# Esquema.net
KiCad netlist of a schematic drawn in EAGLE
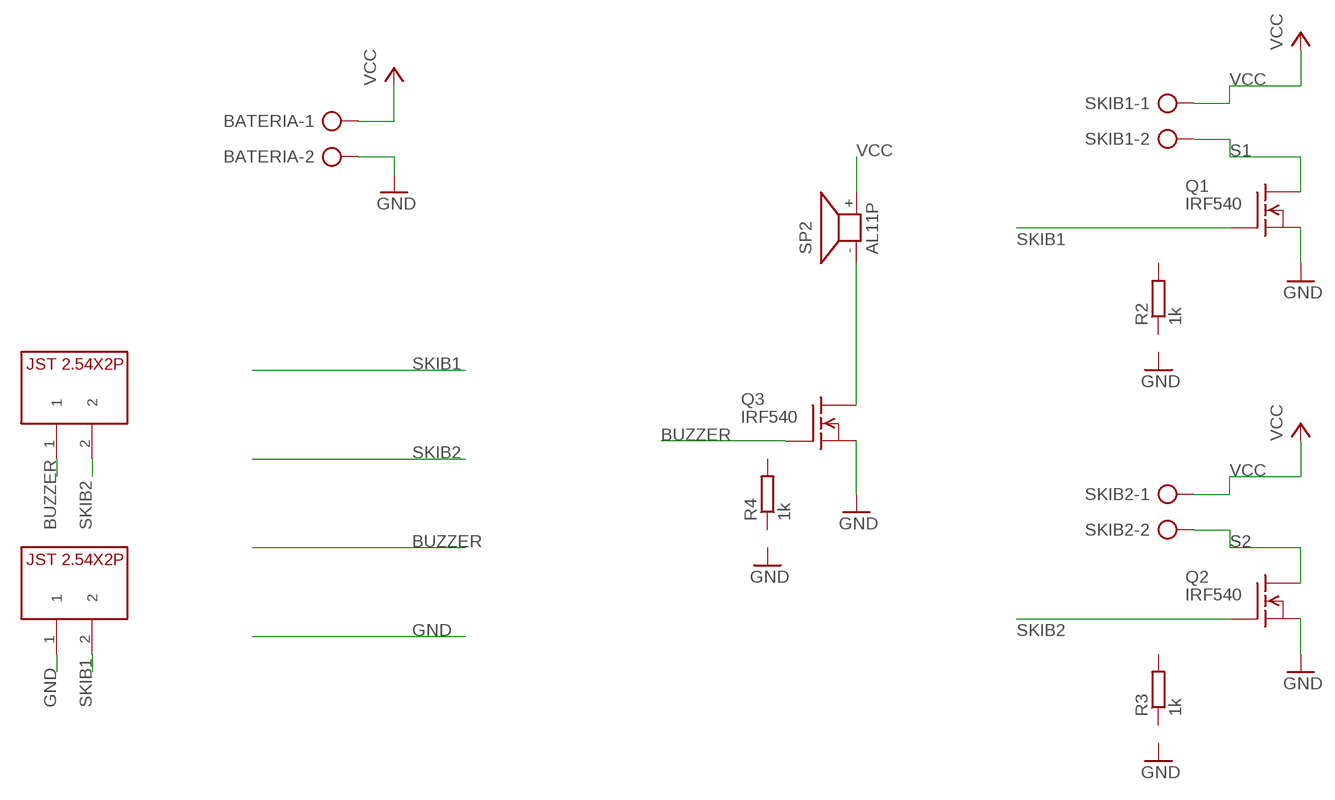
[diagram p0: schematic, sheet 1]

(export (version "E")
  (design (tool "Eeschema 10.0.6"))
  (components
    (comp (ref "BATERIA")
      (value "AK500/2-H")
      (footprint "eagle-import:AK500_2-H")
      (libsource (lib "eagle-import") (part "AK500/2-H"))
    )
    (comp (ref "Q1")
      (value "IRF540")
      (footprint "eagle-import:TO220")
      (libsource (lib "eagle-import") (part "IRF540"))
    )
    (comp (ref "Q2")
      (value "IRF540")
      (footprint "eagle-import:TO220")
      (libsource (lib "eagle-import") (part "IRF540"))
    )
    (comp (ref "Q3")
      (value "IRF540")
      (footprint "eagle-import:TO220")
      (libsource (lib "eagle-import") (part "IRF540"))
    )
    (comp (ref "R2")
      (value "1k")
      (footprint "eagle-import:0207_10")
      (libsource (lib "eagle-import") (part "R-EU_0207/10"))
    )
    (comp (ref "R3")
      (value "1k")
      (footprint "eagle-import:0207_10")
      (libsource (lib "eagle-import") (part "R-EU_0207/10"))
    )
    (comp (ref "R4")
      (value "1k")
      (footprint "eagle-import:0207_10")
      (libsource (lib "eagle-import") (part "R-EU_0207/10"))
    )
    (comp (ref "SKIB1")
      (value "AK500/2-H")
      (footprint "eagle-import:AK500_2-H")
      (libsource (lib "eagle-import") (part "AK500/2-H"))
    )
    (comp (ref "SKIB2")
      (value "AK500/2-H")
      (footprint "eagle-import:AK500_2-H")
      (libsource (lib "eagle-import") (part "AK500/2-H"))
    )
    (comp (ref "SP2")
      (value "AL11P")
      (footprint "eagle-import:AL11P")
      (libsource (lib "eagle-import") (part "AL11P"))
    )
    (comp (ref "U$1")
      (value "JST2.54X2P")
      (footprint "eagle-import:JST2.54X2P_FOOTPRINT")
      (libsource (lib "eagle-import") (part "JST2.54X2P"))
    )
    (comp (ref "U$2")
      (value "JST2.54X2P")
      (footprint "eagle-import:JST2.54X2P_FOOTPRINT")
      (libsource (lib "eagle-import") (part "JST2.54X2P"))
    )
  )
  (nets
    (net (code "1") (name "/BUZZER") (class "Default")
      (node (ref "Q3") (pin "1") (pinfunction "G_1") (pintype "passive"))
      (node (ref "U$1") (pin "1") (pinfunction "1_1") (pintype "bidirectional"))
    )
    (net (code "2") (name "/S1") (class "Default")
      (node (ref "Q1") (pin "2") (pinfunction "D_2") (pintype "passive"))
      (node (ref "SKIB1") (pin "2") (pinfunction "KL_2") (pintype "passive"))
    )
    (net (code "3") (name "/S2") (class "Default")
      (node (ref "Q2") (pin "2") (pinfunction "D_2") (pintype "passive"))
      (node (ref "SKIB2") (pin "2") (pinfunction "KL_2") (pintype "passive"))
    )
    (net (code "4") (name "/SKIB1") (class "Default")
      (node (ref "Q1") (pin "1") (pinfunction "G_1") (pintype "passive"))
      (node (ref "U$2") (pin "2") (pinfunction "2_2") (pintype "bidirectional"))
    )
    (net (code "5") (name "/SKIB2") (class "Default")
      (node (ref "Q2") (pin "1") (pinfunction "G_1") (pintype "passive"))
      (node (ref "U$1") (pin "2") (pinfunction "2_2") (pintype "bidirectional"))
    )
    (net (code "6") (name "GND") (class "Default")
      (node (ref "BATERIA") (pin "2") (pinfunction "KL_2") (pintype "passive"))
      (node (ref "Q1") (pin "3") (pinfunction "S_3") (pintype "passive"))
      (node (ref "Q2") (pin "3") (pinfunction "S_3") (pintype "passive"))
      (node (ref "Q3") (pin "3") (pinfunction "S_3") (pintype "passive"))
      (node (ref "U$2") (pin "1") (pinfunction "1_1") (pintype "bidirectional"))
    )
    (net (code "7") (name "Net-(Q3-D)") (class "Default")
      (node (ref "Q3") (pin "2") (pinfunction "D_2") (pintype "passive"))
      (node (ref "SP2") (pin "-") (pinfunction "1_-") (pintype "passive"))
    )
    (net (code "8") (name "VCC") (class "Default")
      (node (ref "BATERIA") (pin "1") (pinfunction "KL_1") (pintype "passive"))
      (node (ref "SKIB1") (pin "1") (pinfunction "KL_1") (pintype "passive"))
      (node (ref "SKIB2") (pin "1") (pinfunction "KL_1") (pintype "passive"))
      (node (ref "SP2") (pin "+") (pinfunction "2_+") (pintype "passive"))
    )
    (net (code "9") (name "unconnected-(R2-Pad1)") (class "Default")
      (node (ref "R2") (pin "1") (pinfunction "1_1") (pintype "passive"))
    )
    (net (code "10") (name "unconnected-(R2-Pad2)") (class "Default")
      (node (ref "R2") (pin "2") (pinfunction "2_2") (pintype "passive"))
    )
    (net (code "11") (name "unconnected-(R3-Pad1)") (class "Default")
      (node (ref "R3") (pin "1") (pinfunction "1_1") (pintype "passive"))
    )
    (net (code "12") (name "unconnected-(R3-Pad2)") (class "Default")
      (node (ref "R3") (pin "2") (pinfunction "2_2") (pintype "passive"))
    )
    (net (code "13") (name "unconnected-(R4-Pad1)") (class "Default")
      (node (ref "R4") (pin "1") (pinfunction "1_1") (pintype "passive"))
    )
    (net (code "14") (name "unconnected-(R4-Pad2)") (class "Default")
      (node (ref "R4") (pin "2") (pinfunction "2_2") (pintype "passive"))
    )
  )
)
